# MainPCB.net
KiCad netlist of a schematic drawn in Altium Designer
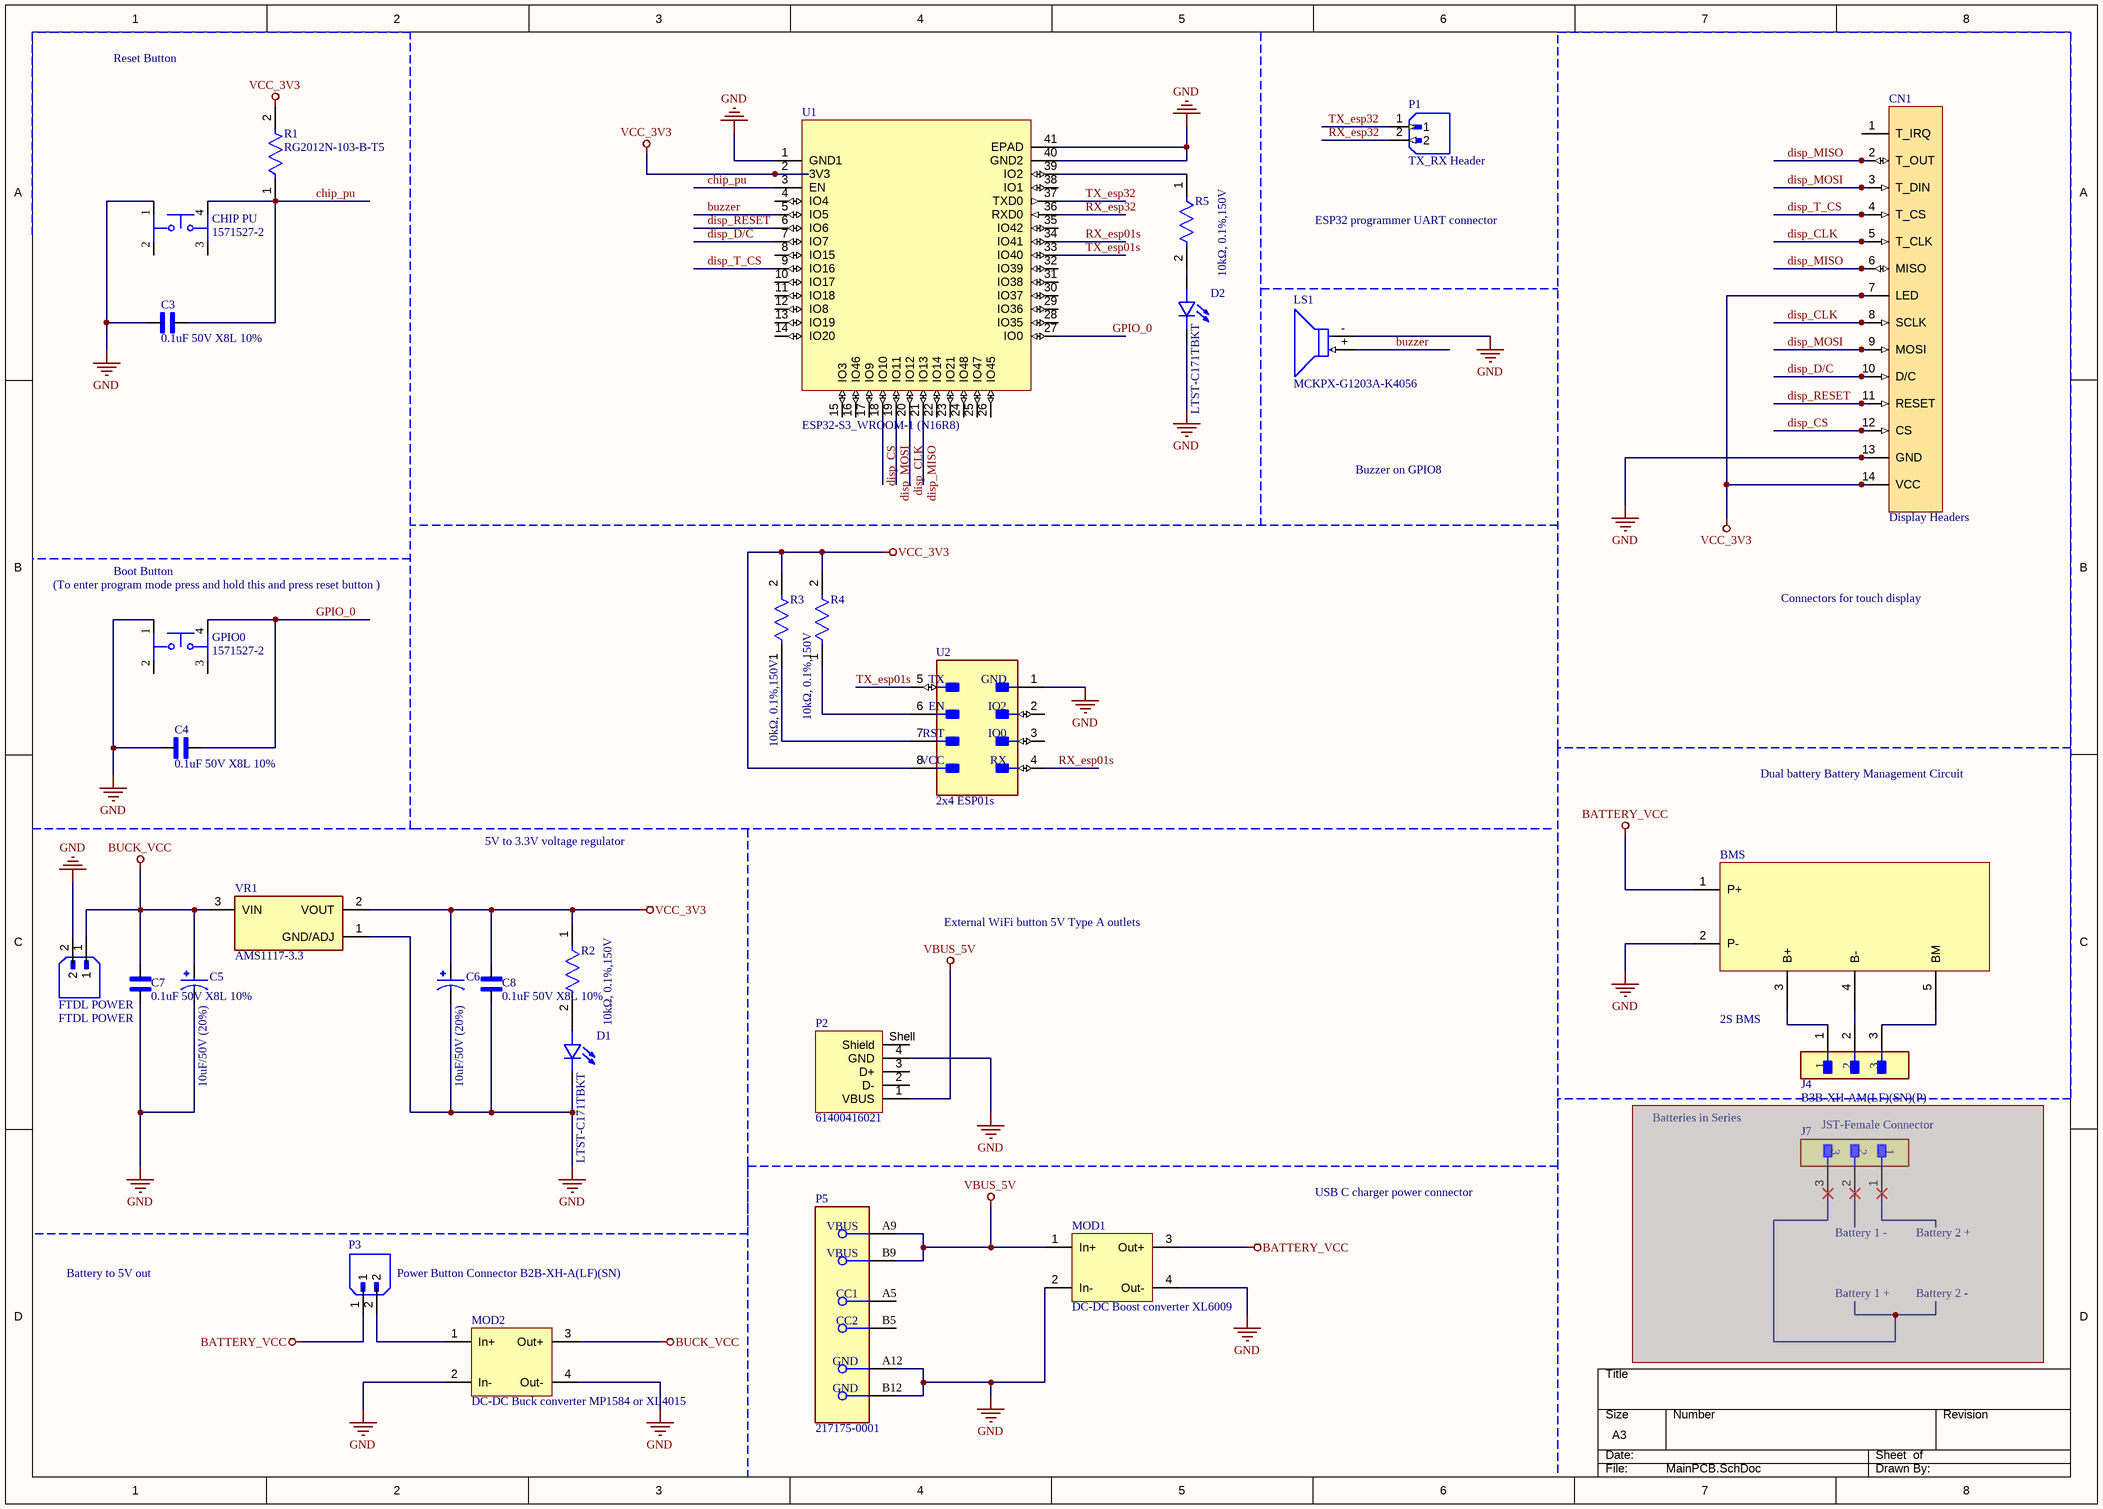
[diagram p0: MainPCB.SchDoc]

(export (version "E")
  (design (tool "Eeschema 10.0.6"))
  (components
    (comp (ref "BMS") (value "2S BMS") (footprint "2S BMS") (libsource (lib "SchemLib") (part "2S BMS")))
    (comp (ref "C3")
      (value "0.1uF 50V X8L 10%")
      (footprint "CAPC2012X145N")
      (description "Cap Ceramic 0.1uF 50V X8L 10% Pad SMD 0805 Soft Termination 150C Automotive T/R")
      (fields (field (name "MF") "Murata") (field (name "MP") "GCJ21BL81H104KA01L"))
      (libsource (lib "") (part "0.1uF 50GCJ21BL81H104KA01LV X8L 10%_1"))
    )
    (comp (ref "C4")
      (value "0.1uF 50V X8L 10%")
      (footprint "CAPC2012X145N")
      (description "Cap Ceramic 0.1uF 50V X8L 10% Pad SMD 0805 Soft Termination 150C Automotive T/R")
      (fields (field (name "MF") "Murata") (field (name "MP") "GCJ21BL81H104KA01L"))
      (libsource (lib "") (part "0.1uF 50GCJ21BL81H104KA01LV X8L 10%_1"))
    )
    (comp (ref "C5")
      (value "10uF/50V (20%)")
      (footprint "CAP_EEE1EA100SR")
      (description "Capacitor 10uF/50V (20%) SMD Electrolytic 5*5.4")
      (libsource (lib "SchemLib") (part "10uF/50V (20%)"))
    )
    (comp (ref "C6")
      (value "10uF/50V (20%)")
      (footprint "CAP_EEE1EA100SR")
      (description "Capacitor 10uF/50V (20%) SMD Electrolytic 5*5.4")
      (libsource (lib "SchemLib") (part "10uF/50V (20%)"))
    )
    (comp (ref "C7")
      (value "0.1uF 50V X8L 10%")
      (footprint "CAPC2012X145N")
      (description "Cap Ceramic 0.1uF 50V X8L 10% Pad SMD 0805 Soft Termination 150C Automotive T/R")
      (fields (field (name "MF") "Murata") (field (name "MP") "GCJ21BL81H104KA01L"))
      (libsource (lib "SchemLib") (part "0.1uF 50GCJ21BL81H104KA01LV X8L 10%"))
    )
    (comp (ref "C8")
      (value "0.1uF 50V X8L 10%")
      (footprint "CAPC2012X145N")
      (description "Cap Ceramic 0.1uF 50V X8L 10% Pad SMD 0805 Soft Termination 150C Automotive T/R")
      (fields (field (name "MF") "Murata") (field (name "MP") "GCJ21BL81H104KA01L"))
      (libsource (lib "SchemLib") (part "0.1uF 50GCJ21BL81H104KA01LV X8L 10%"))
    )
    (comp (ref "CHIP PU")
      (value "1571527-2")
      (footprint "FP-1571527-2-MFG")
      (description "SWITCH TACTILE SPST-NO 0.05A 24V")
      (libsource (lib "SchemLib") (part "SWITCH TACTILE SPST-NO 0.05A 24V"))
    )
    (comp (ref "CN1")
      (value "Display Headers")
      (footprint "Display Without Cutouts")
      (libsource (lib "SchemLib") (part "TFT-LCD-2.8'' Display Headers"))
    )
    (comp (ref "D1")
      (value "LTST-C171TBKT")
      (footprint "DIOC200X125X110")
      (description "Blue 470nm LED Indication - Discrete 3.3V 0805 (2012 Metric)")
      (fields (field (name "MF") "Lite-On Inc."))
      (libsource (lib "SchemLib") (part "LTST-C171TBKT"))
    )
    (comp (ref "D2")
      (value "LTST-C171TBKT")
      (footprint "DIOC200X125X110")
      (description "Blue 470nm LED Indication - Discrete 3.3V 0805 (2012 Metric)")
      (fields (field (name "MF") "Lite-On Inc."))
      (libsource (lib "SchemLib") (part "LTST-C171TBKT"))
    )
    (comp (ref "FTDL POWER")
      (value "FTDL POWER")
      (footprint "JST_B2B-XH-A(LF)(SN)")
      (description "Connector Header Through Hole 2 position 0.098 (2.50mm)")
      (fields (field (name "MF") "JST Sales America Inc.") (field (name "MP") "B2B-XH-A(LF)(SN)"))
      (libsource (lib "") (part "B2B-XH-A(LF)(SN)_1"))
    )
    (comp (ref "GPIO0")
      (value "1571527-2")
      (footprint "FP-1571527-2-MFG")
      (description "SWITCH TACTILE SPST-NO 0.05A 24V")
      (libsource (lib "SchemLib") (part "SWITCH TACTILE SPST-NO 0.05A 24V"))
    )
    (comp (ref "J4")
      (value "B3B-XH-AM(LF)(SN)(P)")
      (footprint "FP-B3B-XH-AM_LF_SN_P-MFG")
      (description "CONN HEADER VERT 3POS 2.5MM")
      (libsource (lib "") (part "JST-XH-3pin_1"))
    )
    (comp (ref "J7")
      (value "JST-Female Connector")
      (footprint "FP-B3B-XH-AM_LF_SN_P-MFG")
      (description "CONN HEADER VERT 3POS 2.5MM")
      (libsource (lib "SchemLib") (part "JST-XH-3pin"))
    )
    (comp (ref "LS1")
      (value "MCKPX-G1203A-K4056")
      (footprint "FP-MCKPX-G1203A-K4056-MFG - duplicate")
      (description "MAGNETIC BUZZER AND TRANSDUCER - More Details")
      (fields
        (field (name "MANUFACTURER") "Multicomp Pro")
        (field (name "OCTOPART") "https://octopart.com/mckpx-g1203a-k4056-multicomp-12157154")
      )
      (libsource (lib "SchemLib") (part "MCKPX-G1203A-K4056"))
    )
    (comp (ref "MOD1")
      (value "DC-DC Boost converter XL6009")
      (footprint "DC-DC boost")
      (libsource (lib "SchemLib") (part "DC-DC Boost converter XL6009"))
    )
    (comp (ref "MOD2")
      (value "DC-DC Buck converter MP1584 or XL4015")
      (footprint "DC-DC boost")
      (libsource (lib "SchemLib") (part "DC-DC Buck converter MP1584 or XL4015"))
    )
    (comp (ref "P1")
      (value "TX_RX Header")
      (footprint "JST_B2B-XH-A(LF)(SN)")
      (libsource (lib "SchemLib") (part "TX_RX Header"))
    )
    (comp (ref "P2")
      (value "61400416021")
      (footprint "61400416021")
      (libsource (lib "SchemLib") (part "Type-A USB"))
    )
    (comp (ref "P3")
      (value "Power Button Connector B2B-XH-A(LF)(SN)")
      (footprint "JST_B2B-XH-A(LF)(SN)")
      (description "Connector Header Through Hole 2 position 0.098 (2.50mm)")
      (fields (field (name "MF") "JST Sales America Inc.") (field (name "MP") "B2B-XH-A(LF)(SN)"))
      (libsource (lib "SchemLib") (part "B2B-XH-A(LF)(SN)"))
    )
    (comp (ref "P5")
      (value "217175-0001")
      (footprint "FP-217175-0001-MFG")
      (description "CONN RCP USB2.0 C 6+18P SMD RA")
      (libsource (lib "SchemLib") (part "Type C USB"))
    )
    (comp (ref "R1")
      (value "RG2012N-103-B-T5")
      (footprint "FP-RG2012-IPC_A")
      (description "Automotive Metal Thin Film Chip Resistor, 0805, 10kΩ, 0.1%, 10ppm/°C, 0.125W, 150V")
      (fields (field (name "TOLERANCE") "0.1%"))
      (libsource (lib "SchemLib") (part "RG2012N-103-B-T5"))
    )
    (comp (ref "R2")
      (value "10kΩ, 0.1%,150V")
      (footprint "FP-RG2012-IPC_A")
      (description "Automotive Metal Thin Film Chip Resistor, 0805, 10kΩ, 0.1%, 10ppm/°C, 0.125W, 150V")
      (fields (field (name "TOLERANCE") "0.1%"))
      (libsource (lib "SchemLib") (part "RG2012N-103-B-T5"))
    )
    (comp (ref "R3")
      (value "10kΩ, 0.1%,150V")
      (footprint "FP-RG2012-IPC_A")
      (description "Automotive Metal Thin Film Chip Resistor, 0805, 10kΩ, 0.1%, 10ppm/°C, 0.125W, 150V")
      (fields (field (name "TOLERANCE") "0.1%"))
      (libsource (lib "SchemLib") (part "RG2012N-103-B-T5"))
    )
    (comp (ref "R4")
      (value "10kΩ, 0.1%,150V")
      (footprint "FP-RG2012-IPC_A")
      (description "Automotive Metal Thin Film Chip Resistor, 0805, 10kΩ, 0.1%, 10ppm/°C, 0.125W, 150V")
      (fields (field (name "TOLERANCE") "0.1%"))
      (libsource (lib "SchemLib") (part "RG2012N-103-B-T5"))
    )
    (comp (ref "R5")
      (value "10kΩ, 0.1%,150V")
      (footprint "FP-RG2012-IPC_A")
      (description "Automotive Metal Thin Film Chip Resistor, 0805, 10kΩ, 0.1%, 10ppm/°C, 0.125W, 150V")
      (fields (field (name "TOLERANCE") "0.1%"))
      (libsource (lib "SchemLib") (part "RG2012N-103-B-T5"))
    )
    (comp (ref "U1")
      (value "ESP32-S3_WROOM-1 (N16R8)")
      (footprint "XCVR_ESP32-S3-WROOM-1-N16R2")
      (libsource (lib "SchemLib") (part "ESP32-S3-WROOM-1-N16R8"))
    )
    (comp (ref "U2")
      (value "2x4 ESP01s")
      (footprint "MODULE_ESP-01")
      (libsource (lib "SchemLib") (part "2x4 ESP01s"))
    )
    (comp (ref "VR1")
      (value "AMS1117-3.3")
      (footprint "SOT229P700X180-4N")
      (description "Sot223/Pkg 1-Amp 3.3-Volt Low Drop Out Voltage Regulatator")
      (fields (field (name "MF") "Advanced Monolithic Systems"))
      (libsource (lib "SchemLib") (part "AMS1117-3.3"))
    )
  )
  (nets
    (net (code "1") (name "/GPIO_0") (class "Default")
      (node (ref "C4") (pin "2") (pinfunction "2_2") (pintype "passive"))
      (node (ref "GPIO0") (pin "4") (pinfunction "4_4") (pintype "passive"))
      (node (ref "U1") (pin "27") (pinfunction "IO0_27") (pintype "bidirectional"))
    )
    (net (code "2") (name "/RX_esp01s") (class "Default")
      (node (ref "U1") (pin "34") (pinfunction "IO41_34") (pintype "bidirectional"))
      (node (ref "U2") (pin "4") (pinfunction "4_4") (pintype "bidirectional"))
    )
    (net (code "3") (name "/RX_esp32") (class "Default")
      (node (ref "P1") (pin "2") (pinfunction "2_2") (pintype "output"))
      (node (ref "U1") (pin "36") (pinfunction "RXD0_36") (pintype "input"))
    )
    (net (code "4") (name "/TX_esp01s") (class "Default")
      (node (ref "U1") (pin "33") (pinfunction "IO40_33") (pintype "bidirectional"))
      (node (ref "U2") (pin "5") (pinfunction "5_5") (pintype "bidirectional"))
    )
    (net (code "5") (name "/TX_esp32") (class "Default")
      (node (ref "P1") (pin "1") (pinfunction "1_1") (pintype "input"))
      (node (ref "U1") (pin "37") (pinfunction "TXD0_37") (pintype "output"))
    )
    (net (code "6") (name "/buzzer") (class "Default")
      (node (ref "LS1") (pin "+") (pinfunction "+_+") (pintype "input"))
      (node (ref "U1") (pin "5") (pinfunction "IO5_5") (pintype "bidirectional"))
    )
    (net (code "7") (name "/chip_pu") (class "Default")
      (node (ref "C3") (pin "2") (pinfunction "2_2") (pintype "passive"))
      (node (ref "CHIP PU") (pin "4") (pinfunction "4_4") (pintype "passive"))
      (node (ref "R1") (pin "1") (pinfunction "1_1") (pintype "passive"))
      (node (ref "U1") (pin "3") (pinfunction "EN_3") (pintype "power_in"))
    )
    (net (code "8") (name "/disp_CLK") (class "Default")
      (node (ref "CN1") (pin "5") (pinfunction "T_CLK_5") (pintype "input"))
      (node (ref "CN1") (pin "8") (pinfunction "SCLK_8") (pintype "input"))
      (node (ref "U1") (pin "20") (pinfunction "IO12_20") (pintype "bidirectional"))
    )
    (net (code "9") (name "/disp_CS") (class "Default")
      (node (ref "CN1") (pin "12") (pinfunction "CS_12") (pintype "input"))
      (node (ref "U1") (pin "18") (pinfunction "IO10_18") (pintype "bidirectional"))
    )
    (net (code "10") (name "/disp_D{slash}C") (class "Default")
      (node (ref "CN1") (pin "10") (pinfunction "D/C_10") (pintype "input"))
      (node (ref "U1") (pin "7") (pinfunction "IO7_7") (pintype "bidirectional"))
    )
    (net (code "11") (name "/disp_MISO") (class "Default")
      (node (ref "CN1") (pin "2") (pinfunction "T_OUT_2") (pintype "bidirectional"))
      (node (ref "CN1") (pin "6") (pinfunction "MISO_6") (pintype "bidirectional"))
      (node (ref "U1") (pin "21") (pinfunction "IO13_21") (pintype "bidirectional"))
    )
    (net (code "12") (name "/disp_MOSI") (class "Default")
      (node (ref "CN1") (pin "3") (pinfunction "T_DIN_3") (pintype "input"))
      (node (ref "CN1") (pin "9") (pinfunction "MOSI_9") (pintype "input"))
      (node (ref "U1") (pin "19") (pinfunction "IO11_19") (pintype "bidirectional"))
    )
    (net (code "13") (name "/disp_RESET") (class "Default")
      (node (ref "CN1") (pin "11") (pinfunction "RESET_11") (pintype "input"))
      (node (ref "U1") (pin "6") (pinfunction "IO6_6") (pintype "bidirectional"))
    )
    (net (code "14") (name "/disp_T_CS") (class "Default")
      (node (ref "CN1") (pin "4") (pinfunction "T_CS_4") (pintype "input"))
      (node (ref "U1") (pin "9") (pinfunction "IO16_9") (pintype "bidirectional"))
    )
    (net (code "15") (name "BATTERY_VCC") (class "Default")
      (node (ref "BMS") (pin "1") (pinfunction "P+_1") (pintype "power_in"))
      (node (ref "MOD1") (pin "3") (pinfunction "Out+_3") (pintype "power_in"))
      (node (ref "P3") (pin "1") (pinfunction "1_1") (pintype "passive"))
    )
    (net (code "16") (name "BUCK_VCC") (class "Default")
      (node (ref "C5") (pin "1") (pinfunction "1_1") (pintype "passive"))
      (node (ref "C7") (pin "2") (pinfunction "2_2") (pintype "passive"))
      (node (ref "FTDL POWER") (pin "1") (pinfunction "1_1") (pintype "passive"))
      (node (ref "MOD2") (pin "3") (pinfunction "Out+_3") (pintype "power_in"))
      (node (ref "VR1") (pin "3") (pinfunction "VIN_3") (pintype "power_in"))
    )
    (net (code "17") (name "GND") (class "Default")
      (node (ref "BMS") (pin "2") (pinfunction "P-_2") (pintype "power_in"))
      (node (ref "C3") (pin "1") (pinfunction "1_1") (pintype "passive"))
      (node (ref "C4") (pin "1") (pinfunction "1_1") (pintype "passive"))
      (node (ref "C5") (pin "2") (pinfunction "2_2") (pintype "passive"))
      (node (ref "C6") (pin "2") (pinfunction "2_2") (pintype "passive"))
      (node (ref "C7") (pin "1") (pinfunction "1_1") (pintype "passive"))
      (node (ref "C8") (pin "1") (pinfunction "1_1") (pintype "passive"))
      (node (ref "CHIP PU") (pin "1") (pinfunction "1_1") (pintype "passive"))
      (node (ref "CN1") (pin "13") (pinfunction "GND_13") (pintype "power_in"))
      (node (ref "D1") (pin "C") (pinfunction "NEG_C") (pintype "passive"))
      (node (ref "D2") (pin "C") (pinfunction "NEG_C") (pintype "passive"))
      (node (ref "FTDL POWER") (pin "2") (pinfunction "2_2") (pintype "passive"))
      (node (ref "GPIO0") (pin "1") (pinfunction "1_1") (pintype "passive"))
      (node (ref "LS1") (pin "-") (pintype "power_in"))
      (node (ref "MOD1") (pin "2") (pinfunction "In-_2") (pintype "power_in"))
      (node (ref "MOD1") (pin "4") (pinfunction "Out-_4") (pintype "power_in"))
      (node (ref "MOD2") (pin "2") (pinfunction "In-_2") (pintype "power_in"))
      (node (ref "MOD2") (pin "4") (pinfunction "Out-_4") (pintype "power_in"))
      (node (ref "P2") (pin "4") (pinfunction "GND_4") (pintype "passive"))
      (node (ref "P5") (pin "A12") (pinfunction "GND_A12") (pintype "power_in"))
      (node (ref "P5") (pin "B12") (pinfunction "GND_B12") (pintype "power_in"))
      (node (ref "U1") (pin "1") (pinfunction "GND1_1") (pintype "power_in"))
      (node (ref "U1") (pin "40") (pinfunction "GND2_40") (pintype "power_in"))
      (node (ref "U1") (pin "41") (pinfunction "EPAD_41") (pintype "power_in"))
      (node (ref "U2") (pin "1") (pinfunction "1_1") (pintype "power_in"))
      (node (ref "VR1") (pin "1") (pinfunction "GND/ADJ_1") (pintype "power_in"))
    )
    (net (code "18") (name "Net-(BMS-B+)") (class "Default")
      (node (ref "BMS") (pin "3") (pinfunction "B+_3") (pintype "power_in"))
      (node (ref "J4") (pin "1") (pinfunction "1_1") (pintype "passive"))
    )
    (net (code "19") (name "Net-(BMS-B-)") (class "Default")
      (node (ref "BMS") (pin "4") (pinfunction "B-_4") (pintype "power_in"))
      (node (ref "J4") (pin "2") (pinfunction "2_2") (pintype "passive"))
    )
    (net (code "20") (name "Net-(BMS-BM)") (class "Default")
      (node (ref "BMS") (pin "5") (pinfunction "BM_5") (pintype "power_in"))
      (node (ref "J4") (pin "3") (pinfunction "3_3") (pintype "passive"))
    )
    (net (code "21") (name "Net-(D1-POS)") (class "Default")
      (node (ref "D1") (pin "A") (pinfunction "POS_A") (pintype "passive"))
      (node (ref "R2") (pin "2") (pinfunction "2_2") (pintype "passive"))
    )
    (net (code "22") (name "Net-(D2-POS)") (class "Default")
      (node (ref "D2") (pin "A") (pinfunction "POS_A") (pintype "passive"))
      (node (ref "R5") (pin "2") (pinfunction "2_2") (pintype "passive"))
    )
    (net (code "23") (name "Net-(MOD2-In+)") (class "Default")
      (node (ref "MOD2") (pin "1") (pinfunction "In+_1") (pintype "power_in"))
      (node (ref "P3") (pin "2") (pinfunction "2_2") (pintype "passive"))
    )
    (net (code "24") (name "Net-(R3-Pad1)") (class "Default")
      (node (ref "R3") (pin "1") (pinfunction "1_1") (pintype "passive"))
      (node (ref "U2") (pin "7") (pinfunction "7_7") (pintype "power_in"))
    )
    (net (code "25") (name "Net-(R4-Pad1)") (class "Default")
      (node (ref "R4") (pin "1") (pinfunction "1_1") (pintype "passive"))
      (node (ref "U2") (pin "6") (pinfunction "6_6") (pintype "power_in"))
    )
    (net (code "26") (name "Net-(U1-IO2)") (class "Default")
      (node (ref "R5") (pin "1") (pinfunction "1_1") (pintype "passive"))
      (node (ref "U1") (pin "39") (pinfunction "IO2_39") (pintype "bidirectional"))
    )
    (net (code "27") (name "VBUS_5V") (class "Default")
      (node (ref "MOD1") (pin "1") (pinfunction "In+_1") (pintype "power_in"))
      (node (ref "P2") (pin "1") (pinfunction "VBUS_1") (pintype "passive"))
      (node (ref "P5") (pin "A9") (pinfunction "VBUS_A9") (pintype "power_in"))
      (node (ref "P5") (pin "B9") (pinfunction "VBUS_B9") (pintype "power_in"))
    )
    (net (code "28") (name "VCC_3V3") (class "Default")
      (node (ref "C6") (pin "1") (pinfunction "1_1") (pintype "passive"))
      (node (ref "C8") (pin "2") (pinfunction "2_2") (pintype "passive"))
      (node (ref "CN1") (pin "14") (pinfunction "VCC_14") (pintype "power_in"))
      (node (ref "CN1") (pin "7") (pinfunction "LED_7") (pintype "power_in"))
      (node (ref "R1") (pin "2") (pinfunction "2_2") (pintype "passive"))
      (node (ref "R2") (pin "1") (pinfunction "1_1") (pintype "passive"))
      (node (ref "R3") (pin "2") (pinfunction "2_2") (pintype "passive"))
      (node (ref "R4") (pin "2") (pinfunction "2_2") (pintype "passive"))
      (node (ref "U1") (pin "2") (pinfunction "3V3_2") (pintype "power_in"))
      (node (ref "U2") (pin "8") (pinfunction "8_8") (pintype "power_in"))
      (node (ref "VR1") (pin "2") (pinfunction "VOUT_2") (pintype "power_in"))
    )
    (net (code "29") (name "unconnected-(CHIP PU-Pad2)") (class "Default")
      (node (ref "CHIP PU") (pin "2") (pinfunction "2_2") (pintype "passive"))
    )
    (net (code "30") (name "unconnected-(CHIP PU-Pad3)") (class "Default")
      (node (ref "CHIP PU") (pin "3") (pinfunction "3_3") (pintype "passive"))
    )
    (net (code "31") (name "unconnected-(CN1-T_IRQ-Pad1)") (class "Default")
      (node (ref "CN1") (pin "1") (pinfunction "T_IRQ_1") (pintype "passive"))
    )
    (net (code "32") (name "unconnected-(GPIO0-Pad2)") (class "Default")
      (node (ref "GPIO0") (pin "2") (pinfunction "2_2") (pintype "passive"))
    )
    (net (code "33") (name "unconnected-(GPIO0-Pad3)") (class "Default")
      (node (ref "GPIO0") (pin "3") (pinfunction "3_3") (pintype "passive"))
    )
    (net (code "34") (name "unconnected-(J7-Pad1)") (class "Default")
      (node (ref "J7") (pin "1") (pinfunction "1_1") (pintype "passive+no_connect"))
    )
    (net (code "35") (name "unconnected-(J7-Pad2)") (class "Default")
      (node (ref "J7") (pin "2") (pinfunction "2_2") (pintype "passive+no_connect"))
    )
    (net (code "36") (name "unconnected-(J7-Pad3)") (class "Default")
      (node (ref "J7") (pin "3") (pinfunction "3_3") (pintype "passive+no_connect"))
    )
    (net (code "37") (name "unconnected-(P2-D+-Pad3)") (class "Default")
      (node (ref "P2") (pin "3") (pinfunction "D+_3") (pintype "passive"))
    )
    (net (code "38") (name "unconnected-(P2-D--Pad2)") (class "Default")
      (node (ref "P2") (pin "2") (pinfunction "D-_2") (pintype "passive"))
    )
    (net (code "39") (name "unconnected-(P2-Shield-PadShell)") (class "Default")
      (node (ref "P2") (pin "Shell") (pinfunction "Shield_Shell") (pintype "passive"))
    )
    (net (code "40") (name "unconnected-(P5-CC1-PadA5)") (class "Default")
      (node (ref "P5") (pin "A5") (pinfunction "CC1_A5") (pintype "passive"))
    )
    (net (code "41") (name "unconnected-(P5-CC2-PadB5)") (class "Default")
      (node (ref "P5") (pin "B5") (pinfunction "CC2_B5") (pintype "passive"))
    )
    (net (code "42") (name "unconnected-(U1-IO1-Pad38)") (class "Default")
      (node (ref "U1") (pin "38") (pinfunction "IO1_38") (pintype "bidirectional"))
    )
    (net (code "43") (name "unconnected-(U1-IO3-Pad15)") (class "Default")
      (node (ref "U1") (pin "15") (pinfunction "IO3_15") (pintype "bidirectional"))
    )
    (net (code "44") (name "unconnected-(U1-IO4-Pad4)") (class "Default")
      (node (ref "U1") (pin "4") (pinfunction "IO4_4") (pintype "bidirectional"))
    )
    (net (code "45") (name "unconnected-(U1-IO8-Pad12)") (class "Default")
      (node (ref "U1") (pin "12") (pinfunction "IO8_12") (pintype "bidirectional"))
    )
    (net (code "46") (name "unconnected-(U1-IO9-Pad17)") (class "Default")
      (node (ref "U1") (pin "17") (pinfunction "IO9_17") (pintype "bidirectional"))
    )
    (net (code "47") (name "unconnected-(U1-IO14-Pad22)") (class "Default")
      (node (ref "U1") (pin "22") (pinfunction "IO14_22") (pintype "bidirectional"))
    )
    (net (code "48") (name "unconnected-(U1-IO15-Pad8)") (class "Default")
      (node (ref "U1") (pin "8") (pinfunction "IO15_8") (pintype "bidirectional"))
    )
    (net (code "49") (name "unconnected-(U1-IO17-Pad10)") (class "Default")
      (node (ref "U1") (pin "10") (pinfunction "IO17_10") (pintype "bidirectional"))
    )
    (net (code "50") (name "unconnected-(U1-IO18-Pad11)") (class "Default")
      (node (ref "U1") (pin "11") (pinfunction "IO18_11") (pintype "bidirectional"))
    )
    (net (code "51") (name "unconnected-(U1-IO19-Pad13)") (class "Default")
      (node (ref "U1") (pin "13") (pinfunction "IO19_13") (pintype "bidirectional"))
    )
    (net (code "52") (name "unconnected-(U1-IO20-Pad14)") (class "Default")
      (node (ref "U1") (pin "14") (pinfunction "IO20_14") (pintype "bidirectional"))
    )
    (net (code "53") (name "unconnected-(U1-IO21-Pad23)") (class "Default")
      (node (ref "U1") (pin "23") (pinfunction "IO21_23") (pintype "bidirectional"))
    )
    (net (code "54") (name "unconnected-(U1-IO35-Pad28)") (class "Default")
      (node (ref "U1") (pin "28") (pinfunction "IO35_28") (pintype "bidirectional"))
    )
    (net (code "55") (name "unconnected-(U1-IO36-Pad29)") (class "Default")
      (node (ref "U1") (pin "29") (pinfunction "IO36_29") (pintype "bidirectional"))
    )
    (net (code "56") (name "unconnected-(U1-IO37-Pad30)") (class "Default")
      (node (ref "U1") (pin "30") (pinfunction "IO37_30") (pintype "bidirectional"))
    )
    (net (code "57") (name "unconnected-(U1-IO38-Pad31)") (class "Default")
      (node (ref "U1") (pin "31") (pinfunction "IO38_31") (pintype "bidirectional"))
    )
    (net (code "58") (name "unconnected-(U1-IO39-Pad32)") (class "Default")
      (node (ref "U1") (pin "32") (pinfunction "IO39_32") (pintype "bidirectional"))
    )
    (net (code "59") (name "unconnected-(U1-IO42-Pad35)") (class "Default")
      (node (ref "U1") (pin "35") (pinfunction "IO42_35") (pintype "bidirectional"))
    )
    (net (code "60") (name "unconnected-(U1-IO45-Pad26)") (class "Default")
      (node (ref "U1") (pin "26") (pinfunction "IO45_26") (pintype "bidirectional"))
    )
    (net (code "61") (name "unconnected-(U1-IO46-Pad16)") (class "Default")
      (node (ref "U1") (pin "16") (pinfunction "IO46_16") (pintype "bidirectional"))
    )
    (net (code "62") (name "unconnected-(U1-IO47-Pad25)") (class "Default")
      (node (ref "U1") (pin "25") (pinfunction "IO47_25") (pintype "bidirectional"))
    )
    (net (code "63") (name "unconnected-(U1-IO48-Pad24)") (class "Default")
      (node (ref "U1") (pin "24") (pinfunction "IO48_24") (pintype "bidirectional"))
    )
    (net (code "64") (name "unconnected-(U2-Pad2)") (class "Default")
      (node (ref "U2") (pin "2") (pinfunction "2_2") (pintype "bidirectional"))
    )
    (net (code "65") (name "unconnected-(U2-Pad3)") (class "Default")
      (node (ref "U2") (pin "3") (pinfunction "3_3") (pintype "bidirectional"))
    )
  )
)
